# 05_LMS7002M_1_RF.net
KiCad netlist of a schematic drawn in Altium Designer
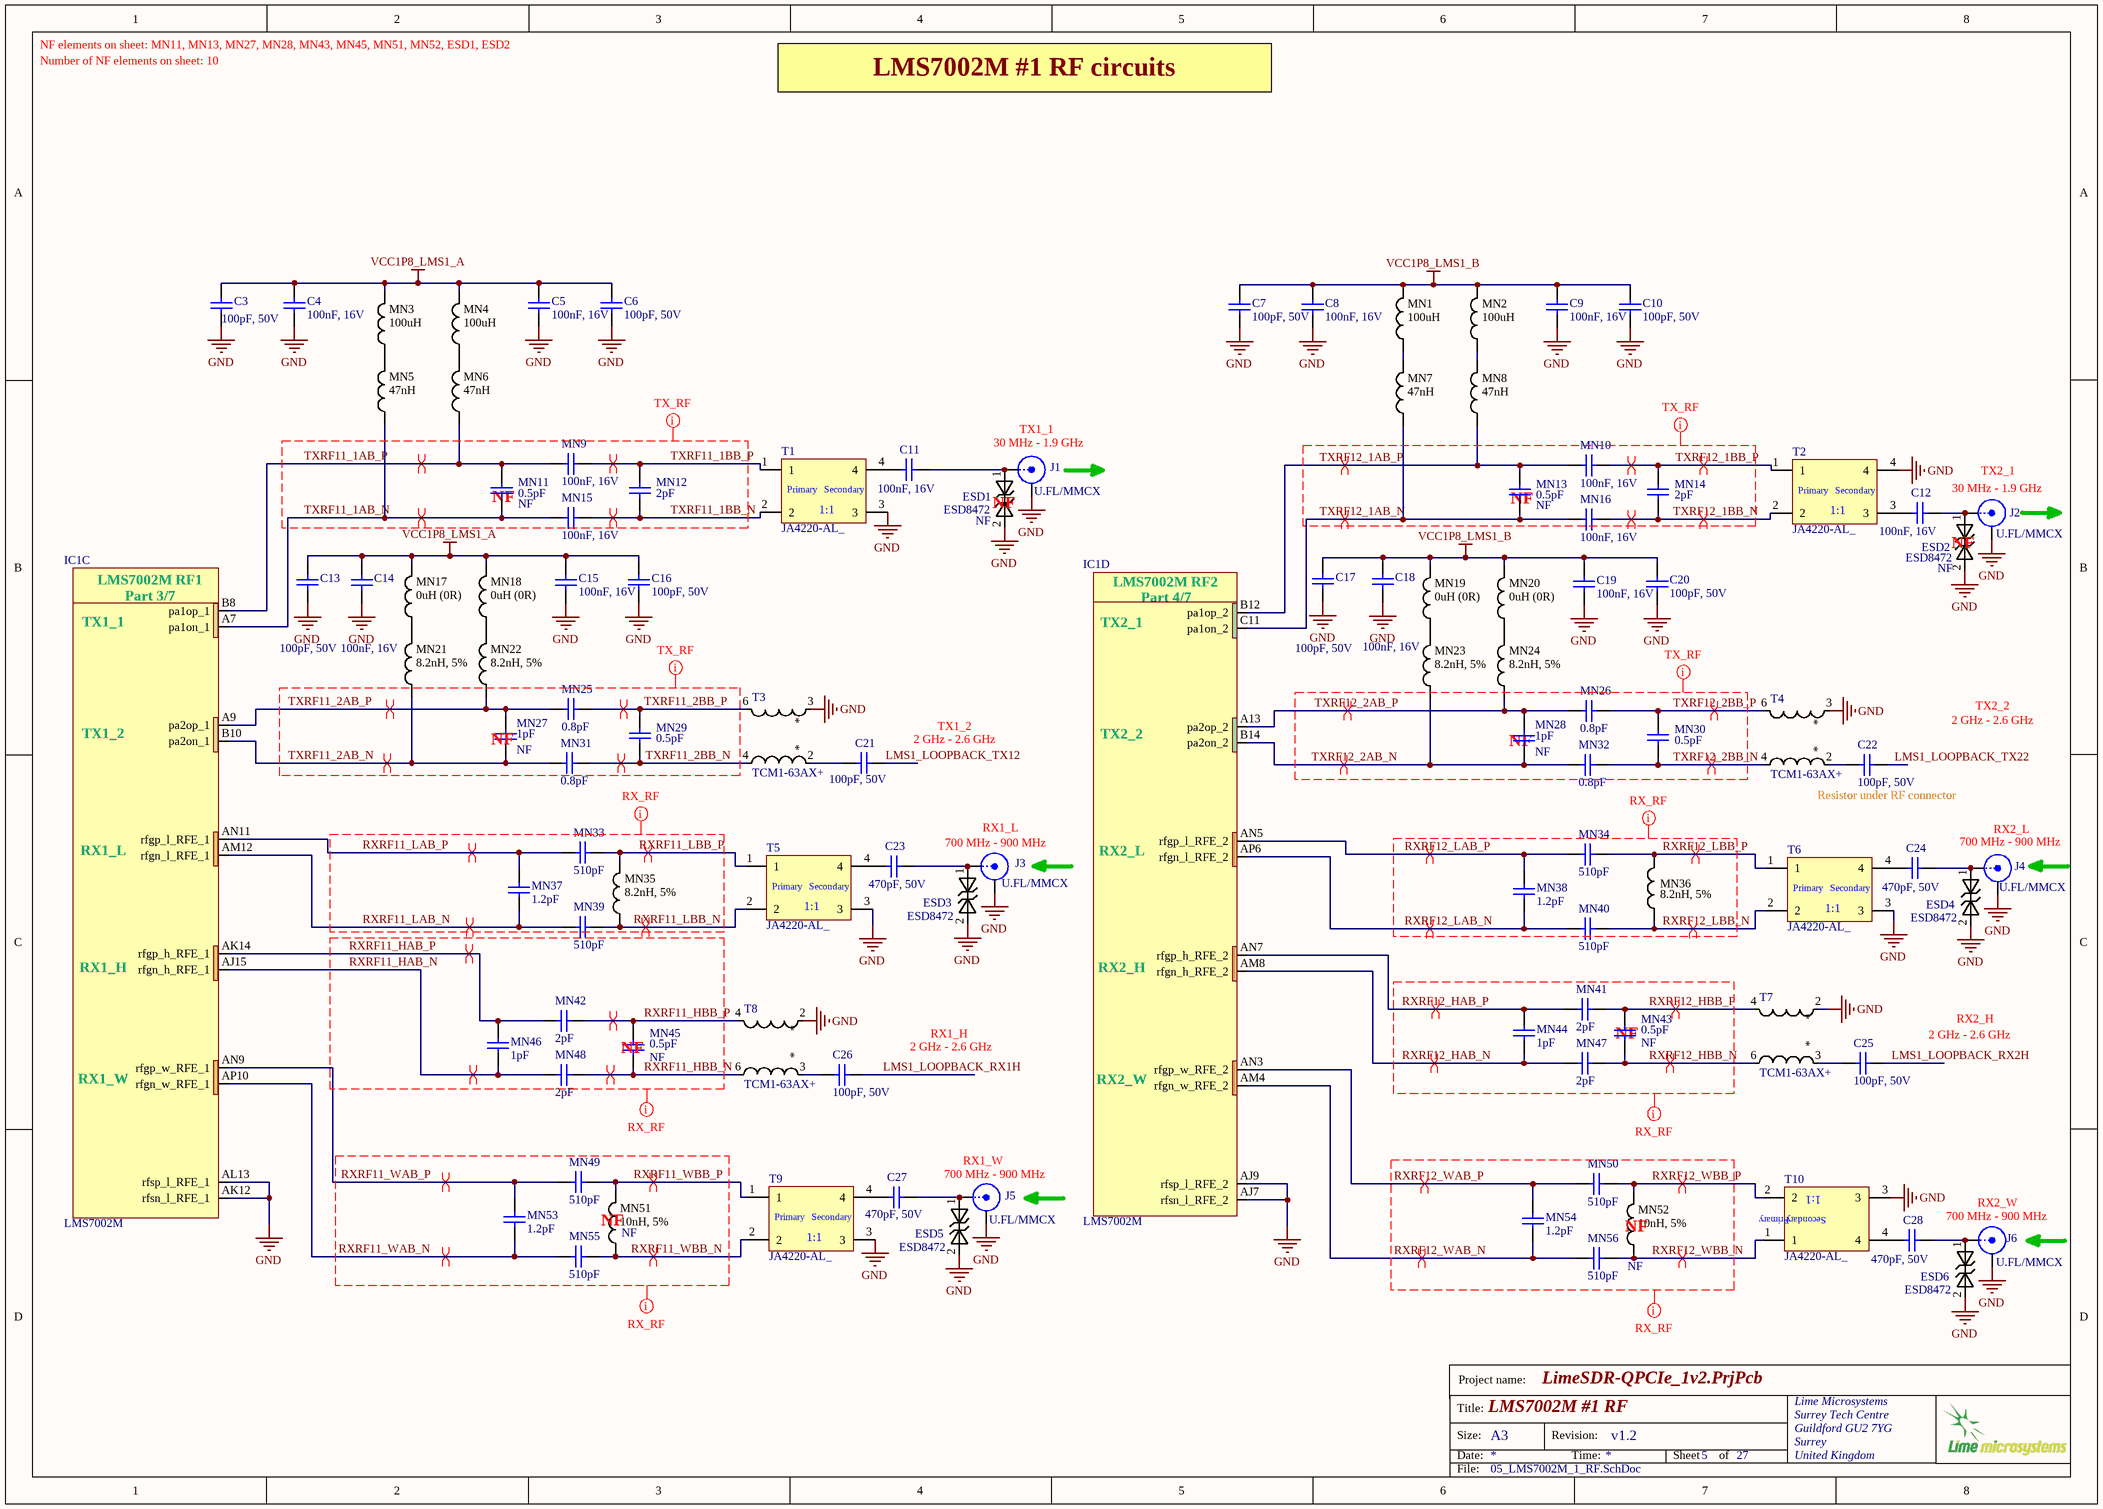
[diagram p0: 05_LMS7002M_1_RF.SchDoc]

(export (version "E")
  (design (tool "Eeschema 10.0.6"))
  (components
    (comp (ref "C3")
      (value "100pF, 50V")
      (footprint "CAP0402")
      (fields (field (name "MANUFACTURER") "Yageo") (field (name "TOLERANCE") "±5%"))
      (libsource (lib "LimeMicroAltiumLib_schLib") (part "Cap_0402"))
    )
    (comp (ref "C4")
      (value "100nF, 16V")
      (footprint "CAP0402")
      (fields
        (field (name "MANUFACTURER") "Murata Electronics")
        (field (name "TOLERANCE") "10 %")
        (field (name "MANUFACTURER PART NUMBER") "GRM155R71C104KA88D")
      )
      (libsource (lib "LimeMicroAltiumLib_schLib") (part "Cap_0402"))
    )
    (comp (ref "C5")
      (value "100nF, 16V")
      (footprint "CAP0402")
      (fields
        (field (name "MANUFACTURER") "Murata Electronics")
        (field (name "TOLERANCE") "10 %")
        (field (name "MANUFACTURER PART NUMBER") "GRM155R71C104KA88D")
      )
      (libsource (lib "LimeMicroAltiumLib_schLib") (part "Cap_0402"))
    )
    (comp (ref "C6")
      (value "100pF, 50V")
      (footprint "CAP0402")
      (fields (field (name "MANUFACTURER") "Yageo") (field (name "TOLERANCE") "±5%"))
      (libsource (lib "LimeMicroAltiumLib_schLib") (part "Cap_0402"))
    )
    (comp (ref "C7")
      (value "100pF, 50V")
      (footprint "CAP0402")
      (fields (field (name "MANUFACTURER") "Yageo") (field (name "TOLERANCE") "±5%"))
      (libsource (lib "LimeMicroAltiumLib_schLib") (part "Cap_0402"))
    )
    (comp (ref "C8")
      (value "100nF, 16V")
      (footprint "CAP0402")
      (fields
        (field (name "MANUFACTURER") "Murata Electronics")
        (field (name "TOLERANCE") "10 %")
        (field (name "MANUFACTURER PART NUMBER") "GRM155R71C104KA88D")
      )
      (libsource (lib "LimeMicroAltiumLib_schLib") (part "Cap_0402"))
    )
    (comp (ref "C9")
      (value "100nF, 16V")
      (footprint "CAP0402")
      (fields
        (field (name "MANUFACTURER") "Murata Electronics")
        (field (name "TOLERANCE") "10 %")
        (field (name "MANUFACTURER PART NUMBER") "GRM155R71C104KA88D")
      )
      (libsource (lib "LimeMicroAltiumLib_schLib") (part "Cap_0402"))
    )
    (comp (ref "C10")
      (value "100pF, 50V")
      (footprint "CAP0402")
      (fields (field (name "MANUFACTURER") "Yageo") (field (name "TOLERANCE") "±5%"))
      (libsource (lib "LimeMicroAltiumLib_schLib") (part "Cap_0402"))
    )
    (comp (ref "C11")
      (value "100nF, 16V")
      (footprint "CAP0402")
      (fields
        (field (name "MANUFACTURER") "Murata Electronics")
        (field (name "TOLERANCE") "10 %")
        (field (name "MANUFACTURER PART NUMBER") "GRM155R71C104KA88D")
      )
      (libsource (lib "LimeMicroAltiumLib_schLib") (part "Cap_0402"))
    )
    (comp (ref "C12")
      (value "100nF, 16V")
      (footprint "CAP0402")
      (fields
        (field (name "MANUFACTURER") "Murata Electronics")
        (field (name "TOLERANCE") "10 %")
        (field (name "MANUFACTURER PART NUMBER") "GRM155R71C104KA88D")
      )
      (libsource (lib "LimeMicroAltiumLib_schLib") (part "Cap_0402"))
    )
    (comp (ref "C13")
      (value "100pF, 50V")
      (footprint "CAP0402")
      (fields (field (name "MANUFACTURER") "Yageo") (field (name "TOLERANCE") "±5%"))
      (libsource (lib "LimeMicroAltiumLib_schLib") (part "Cap_0402"))
    )
    (comp (ref "C14")
      (value "100nF, 16V")
      (footprint "CAP0402")
      (fields
        (field (name "MANUFACTURER") "Murata Electronics")
        (field (name "TOLERANCE") "10 %")
        (field (name "MANUFACTURER PART NUMBER") "GRM155R71C104KA88D")
      )
      (libsource (lib "LimeMicroAltiumLib_schLib") (part "Cap_0402"))
    )
    (comp (ref "C15")
      (value "100nF, 16V")
      (footprint "CAP0402")
      (fields
        (field (name "MANUFACTURER") "Murata Electronics")
        (field (name "TOLERANCE") "10 %")
        (field (name "MANUFACTURER PART NUMBER") "GRM155R71C104KA88D")
      )
      (libsource (lib "LimeMicroAltiumLib_schLib") (part "Cap_0402"))
    )
    (comp (ref "C16")
      (value "100pF, 50V")
      (footprint "CAP0402")
      (fields (field (name "MANUFACTURER") "Yageo") (field (name "TOLERANCE") "±5%"))
      (libsource (lib "LimeMicroAltiumLib_schLib") (part "Cap_0402"))
    )
    (comp (ref "C17")
      (value "100pF, 50V")
      (footprint "CAP0402")
      (fields (field (name "MANUFACTURER") "Yageo") (field (name "TOLERANCE") "±5%"))
      (libsource (lib "LimeMicroAltiumLib_schLib") (part "Cap_0402"))
    )
    (comp (ref "C18")
      (value "100nF, 16V")
      (footprint "CAP0402")
      (fields
        (field (name "MANUFACTURER") "Murata Electronics")
        (field (name "TOLERANCE") "10 %")
        (field (name "MANUFACTURER PART NUMBER") "GRM155R71C104KA88D")
      )
      (libsource (lib "LimeMicroAltiumLib_schLib") (part "Cap_0402"))
    )
    (comp (ref "C19")
      (value "100nF, 16V")
      (footprint "CAP0402")
      (fields
        (field (name "MANUFACTURER") "Murata Electronics")
        (field (name "TOLERANCE") "10 %")
        (field (name "MANUFACTURER PART NUMBER") "GRM155R71C104KA88D")
      )
      (libsource (lib "LimeMicroAltiumLib_schLib") (part "Cap_0402"))
    )
    (comp (ref "C20")
      (value "100pF, 50V")
      (footprint "CAP0402")
      (fields (field (name "MANUFACTURER") "Yageo") (field (name "TOLERANCE") "±5%"))
      (libsource (lib "LimeMicroAltiumLib_schLib") (part "Cap_0402"))
    )
    (comp (ref "C21")
      (value "100pF, 50V")
      (footprint "CAP0402")
      (fields (field (name "TOLERANCE") "±5%") (field (name "MANUFACTURER") "Yageo"))
      (libsource (lib "LimeMicroAltiumLib_schLib") (part "Cap_0402"))
    )
    (comp (ref "C22")
      (value "100pF, 50V")
      (footprint "CAP0402")
      (fields (field (name "TOLERANCE") "±5%") (field (name "MANUFACTURER") "Yageo"))
      (libsource (lib "LimeMicroAltiumLib_schLib") (part "Cap_0402"))
    )
    (comp (ref "C23")
      (value "470pF, 50V")
      (footprint "CAP0402")
      (fields
        (field (name "MANUFACTURER PART NUMBER") "C1005C0G1H471J050BA")
        (field (name "TOLERANCE") "±5%")
        (field (name "MANUFACTURER") "TDK Corporation")
      )
      (libsource (lib "LimeMicroAltiumLib_schLib") (part "Cap_0402"))
    )
    (comp (ref "C24")
      (value "470pF, 50V")
      (footprint "CAP0402")
      (fields
        (field (name "MANUFACTURER PART NUMBER") "C1005C0G1H471J050BA")
        (field (name "TOLERANCE") "±5%")
        (field (name "MANUFACTURER") "TDK Corporation")
      )
      (libsource (lib "LimeMicroAltiumLib_schLib") (part "Cap_0402"))
    )
    (comp (ref "C25")
      (value "100pF, 50V")
      (footprint "CAP0402")
      (fields (field (name "TOLERANCE") "±5%") (field (name "MANUFACTURER") "Yageo"))
      (libsource (lib "LimeMicroAltiumLib_schLib") (part "Cap_0402"))
    )
    (comp (ref "C26")
      (value "100pF, 50V")
      (footprint "CAP0402")
      (fields (field (name "TOLERANCE") "±5%") (field (name "MANUFACTURER") "Yageo"))
      (libsource (lib "LimeMicroAltiumLib_schLib") (part "Cap_0402"))
    )
    (comp (ref "C27")
      (value "470pF, 50V")
      (footprint "CAP0402")
      (fields
        (field (name "MANUFACTURER PART NUMBER") "C1005C0G1H471J050BA")
        (field (name "TOLERANCE") "±5%")
        (field (name "MANUFACTURER") "TDK Corporation")
      )
      (libsource (lib "LimeMicroAltiumLib_schLib") (part "Cap_0402"))
    )
    (comp (ref "C28")
      (value "470pF, 50V")
      (footprint "CAP0402")
      (fields
        (field (name "MANUFACTURER PART NUMBER") "C1005C0G1H471J050BA")
        (field (name "TOLERANCE") "±5%")
        (field (name "MANUFACTURER") "TDK Corporation")
      )
      (libsource (lib "LimeMicroAltiumLib_schLib") (part "Cap_0402"))
    )
    (comp (ref "ESD1")
      (value "ESD8472")
      (footprint "ESD8472_X3DFN2")
      (fields
        (field (name "MANUFACTURER") "ON Semiconductor")
        (field (name "MANUFACTURER PART NUMBER") "ESD8472MUT5G")
        (field (name "ASSEMBLY INFO") "NF")
      )
      (libsource (lib "LimeMicroAltiumLib_schLib") (part "ESD8472"))
    )
    (comp (ref "ESD2")
      (value "ESD8472")
      (footprint "ESD8472_X3DFN2")
      (fields
        (field (name "MANUFACTURER") "ON Semiconductor")
        (field (name "MANUFACTURER PART NUMBER") "ESD8472MUT5G")
        (field (name "ASSEMBLY INFO") "NF")
      )
      (libsource (lib "LimeMicroAltiumLib_schLib") (part "ESD8472"))
    )
    (comp (ref "ESD3")
      (value "ESD8472")
      (footprint "ESD8472_X3DFN2")
      (fields
        (field (name "MANUFACTURER") "ON Semiconductor")
        (field (name "MANUFACTURER PART NUMBER") "ESD8472MUT5G")
      )
      (libsource (lib "LimeMicroAltiumLib_schLib") (part "ESD8472"))
    )
    (comp (ref "ESD4")
      (value "ESD8472")
      (footprint "ESD8472_X3DFN2")
      (fields
        (field (name "MANUFACTURER") "ON Semiconductor")
        (field (name "MANUFACTURER PART NUMBER") "ESD8472MUT5G")
      )
      (libsource (lib "LimeMicroAltiumLib_schLib") (part "ESD8472"))
    )
    (comp (ref "ESD5")
      (value "ESD8472")
      (footprint "ESD8472_X3DFN2")
      (fields
        (field (name "MANUFACTURER") "ON Semiconductor")
        (field (name "MANUFACTURER PART NUMBER") "ESD8472MUT5G")
      )
      (libsource (lib "LimeMicroAltiumLib_schLib") (part "ESD8472"))
    )
    (comp (ref "ESD6")
      (value "ESD8472")
      (footprint "ESD8472_X3DFN2")
      (fields
        (field (name "MANUFACTURER") "ON Semiconductor")
        (field (name "MANUFACTURER PART NUMBER") "ESD8472MUT5G")
      )
      (libsource (lib "LimeMicroAltiumLib_schLib") (part "ESD8472"))
    )
    (comp (ref "IC1")
      (value "LMS7002M")
      (footprint "LMS7002M_v4")
      (description "Schematic symbol revision 3. Default footprint - 0.31mm pad")
      (fields (field (name "MANUFACTURER") "Lime Microsystems"))
      (libsource (lib "LimeMicroAltiumLib_schLib") (part "LMS7002Mr3"))
    )
    (comp (ref "J1")
      (value "U.FL/MMCX")
      (footprint "MMCX_UFL_conn_u")
      (description "CONN UMC RCPT STR 50 OHM SMD")
      (fields (field (name "MANUFACTURER") "Molex, LLC"))
      (libsource (lib "LimeMicroAltiumLib_schLib") (part "RF_IF_connector"))
    )
    (comp (ref "J2")
      (value "U.FL/MMCX")
      (footprint "MMCX_UFL_conn_u")
      (description "CONN UMC RCPT STR 50 OHM SMD")
      (fields (field (name "MANUFACTURER") "Molex, LLC"))
      (libsource (lib "LimeMicroAltiumLib_schLib") (part "RF_IF_connector"))
    )
    (comp (ref "J3")
      (value "U.FL/MMCX")
      (footprint "MMCX_UFL_conn_u")
      (description "CONN UMC RCPT STR 50 OHM SMD")
      (fields (field (name "MANUFACTURER") "Molex, LLC"))
      (libsource (lib "LimeMicroAltiumLib_schLib") (part "RF_IF_connector"))
    )
    (comp (ref "J4")
      (value "U.FL/MMCX")
      (footprint "MMCX_UFL_conn_u")
      (description "CONN UMC RCPT STR 50 OHM SMD")
      (fields (field (name "MANUFACTURER") "Molex, LLC"))
      (libsource (lib "LimeMicroAltiumLib_schLib") (part "RF_IF_connector"))
    )
    (comp (ref "J5")
      (value "U.FL/MMCX")
      (footprint "MMCX_UFL_conn_u")
      (description "CONN UMC RCPT STR 50 OHM SMD")
      (fields (field (name "MANUFACTURER") "Molex, LLC"))
      (libsource (lib "LimeMicroAltiumLib_schLib") (part "RF_IF_connector"))
    )
    (comp (ref "J6")
      (value "U.FL/MMCX")
      (footprint "MMCX_UFL_conn_u")
      (description "CONN UMC RCPT STR 50 OHM SMD")
      (fields (field (name "MANUFACTURER") "Molex, LLC"))
      (libsource (lib "LimeMicroAltiumLib_schLib") (part "RF_IF_connector"))
    )
    (comp (ref "MN1")
      (value "100uH")
      (footprint "RES0805")
      (fields
        (field (name "TOLERANCE") "±10%")
        (field (name "MANUFACTURER") "TDK Corporation")
        (field (name "MANUFACTURER PART NUMBER") "MLF2012C101KT000")
      )
      (libsource (lib "LimeMicroAltiumLib_schLib") (part "Inductor_0603"))
    )
    (comp (ref "MN2")
      (value "100uH")
      (footprint "RES0805")
      (fields
        (field (name "TOLERANCE") "±10%")
        (field (name "MANUFACTURER") "TDK Corporation")
        (field (name "MANUFACTURER PART NUMBER") "MLF2012C101KT000")
      )
      (libsource (lib "LimeMicroAltiumLib_schLib") (part "Inductor_0603"))
    )
    (comp (ref "MN3")
      (value "100uH")
      (footprint "RES0805")
      (fields
        (field (name "TOLERANCE") "±10%")
        (field (name "MANUFACTURER") "TDK Corporation")
        (field (name "MANUFACTURER PART NUMBER") "MLF2012C101KT000")
      )
      (libsource (lib "LimeMicroAltiumLib_schLib") (part "Inductor_0603"))
    )
    (comp (ref "MN4")
      (value "100uH")
      (footprint "RES0805")
      (fields
        (field (name "TOLERANCE") "±10%")
        (field (name "MANUFACTURER") "TDK Corporation")
        (field (name "MANUFACTURER PART NUMBER") "MLF2012C101KT000")
      )
      (libsource (lib "LimeMicroAltiumLib_schLib") (part "Inductor_0603"))
    )
    (comp (ref "MN5")
      (value "47nH")
      (footprint "RES0402")
      (fields
        (field (name "MANUFACTURER") "COILCRAFT")
        (field (name "MANUFACTURER PART NUMBER") "0402HP-47NXJLU")
      )
      (libsource (lib "LimeMicroAltiumLib_schLib") (part "Inductor_0603"))
    )
    (comp (ref "MN6")
      (value "47nH")
      (footprint "RES0402")
      (fields
        (field (name "MANUFACTURER") "COILCRAFT")
        (field (name "MANUFACTURER PART NUMBER") "0402HP-47NXJLU")
      )
      (libsource (lib "LimeMicroAltiumLib_schLib") (part "Inductor_0603"))
    )
    (comp (ref "MN7")
      (value "47nH")
      (footprint "RES0402")
      (fields
        (field (name "MANUFACTURER") "COILCRAFT")
        (field (name "MANUFACTURER PART NUMBER") "0402HP-47NXJLU")
      )
      (libsource (lib "LimeMicroAltiumLib_schLib") (part "Inductor_0603"))
    )
    (comp (ref "MN8")
      (value "47nH")
      (footprint "RES0402")
      (fields
        (field (name "MANUFACTURER") "COILCRAFT")
        (field (name "MANUFACTURER PART NUMBER") "0402HP-47NXJLU")
      )
      (libsource (lib "LimeMicroAltiumLib_schLib") (part "Inductor_0603"))
    )
    (comp (ref "MN9")
      (value "100nF, 16V")
      (footprint "CAP0402")
      (fields
        (field (name "MANUFACTURER") "Murata Electronics")
        (field (name "TOLERANCE") "10 %")
        (field (name "MANUFACTURER PART NUMBER") "GRM155R71C104KA88D")
      )
      (libsource (lib "LimeMicroAltiumLib_schLib") (part "Cap_0402"))
    )
    (comp (ref "MN10")
      (value "100nF, 16V")
      (footprint "CAP0402")
      (fields
        (field (name "MANUFACTURER") "Murata Electronics")
        (field (name "TOLERANCE") "10 %")
        (field (name "MANUFACTURER PART NUMBER") "GRM155R71C104KA88D")
      )
      (libsource (lib "LimeMicroAltiumLib_schLib") (part "Cap_0402"))
    )
    (comp (ref "MN11")
      (value "0.5pF")
      (footprint "CAP0402")
      (fields
        (field (name "ASSEMBLY INFO") "NF")
        (field (name "TOLERANCE") "±0.25pF")
        (field (name "MANUFACTURER") "Yageo")
      )
      (libsource (lib "LimeMicroAltiumLib_schLib") (part "Cap_0402"))
    )
    (comp (ref "MN12")
      (value "2pF")
      (footprint "CAP0402")
      (fields (field (name "MANUFACTURER") "AVX"))
      (libsource (lib "LimeMicroAltiumLib_schLib") (part "Cap_0402"))
    )
    (comp (ref "MN13")
      (value "0.5pF")
      (footprint "CAP0402")
      (fields
        (field (name "ASSEMBLY INFO") "NF")
        (field (name "TOLERANCE") "±0.25pF")
        (field (name "MANUFACTURER") "Yageo")
      )
      (libsource (lib "LimeMicroAltiumLib_schLib") (part "Cap_0402"))
    )
    (comp (ref "MN14")
      (value "2pF")
      (footprint "CAP0402")
      (fields (field (name "MANUFACTURER") "AVX"))
      (libsource (lib "LimeMicroAltiumLib_schLib") (part "Cap_0402"))
    )
    (comp (ref "MN15")
      (value "100nF, 16V")
      (footprint "CAP0402")
      (fields
        (field (name "MANUFACTURER") "Murata Electronics")
        (field (name "TOLERANCE") "10 %")
        (field (name "MANUFACTURER PART NUMBER") "GRM155R71C104KA88D")
      )
      (libsource (lib "LimeMicroAltiumLib_schLib") (part "Cap_0402"))
    )
    (comp (ref "MN16")
      (value "100nF, 16V")
      (footprint "CAP0402")
      (fields
        (field (name "MANUFACTURER") "Murata Electronics")
        (field (name "TOLERANCE") "10 %")
        (field (name "MANUFACTURER PART NUMBER") "GRM155R71C104KA88D")
      )
      (libsource (lib "LimeMicroAltiumLib_schLib") (part "Cap_0402"))
    )
    (comp (ref "MN17")
      (value "0uH (0R)")
      (footprint "RES0805")
      (fields (field (name "MANUFACTURER") "BOURNS"))
      (libsource (lib "LimeMicroAltiumLib_schLib") (part "Inductor_0603"))
    )
    (comp (ref "MN18")
      (value "0uH (0R)")
      (footprint "RES0805")
      (fields (field (name "MANUFACTURER") "BOURNS"))
      (libsource (lib "LimeMicroAltiumLib_schLib") (part "Inductor_0603"))
    )
    (comp (ref "MN19")
      (value "0uH (0R)")
      (footprint "RES0805")
      (fields (field (name "MANUFACTURER") "BOURNS"))
      (libsource (lib "LimeMicroAltiumLib_schLib") (part "Inductor_0603"))
    )
    (comp (ref "MN20")
      (value "0uH (0R)")
      (footprint "RES0805")
      (fields (field (name "MANUFACTURER") "BOURNS"))
      (libsource (lib "LimeMicroAltiumLib_schLib") (part "Inductor_0603"))
    )
    (comp (ref "MN21")
      (value "8.2nH, 5%")
      (footprint "RES0402")
      (fields (field (name "MANUFACTURER") "COILCRAFT"))
      (libsource (lib "LimeMicroAltiumLib_schLib") (part "Inductor_0603"))
    )
    (comp (ref "MN22")
      (value "8.2nH, 5%")
      (footprint "RES0402")
      (fields (field (name "MANUFACTURER") "COILCRAFT"))
      (libsource (lib "LimeMicroAltiumLib_schLib") (part "Inductor_0603"))
    )
    (comp (ref "MN23")
      (value "8.2nH, 5%")
      (footprint "RES0402")
      (fields (field (name "MANUFACTURER") "COILCRAFT"))
      (libsource (lib "LimeMicroAltiumLib_schLib") (part "Inductor_0603"))
    )
    (comp (ref "MN24")
      (value "8.2nH, 5%")
      (footprint "RES0402")
      (fields (field (name "MANUFACTURER") "COILCRAFT"))
      (libsource (lib "LimeMicroAltiumLib_schLib") (part "Inductor_0603"))
    )
    (comp (ref "MN25")
      (value "0.8pF")
      (footprint "CAP0402")
      (fields
        (field (name "TOLERANCE") "±0.1pF")
        (field (name "MANUFACTURER") "Murata Electronics North America")
      )
      (libsource (lib "LimeMicroAltiumLib_schLib") (part "Cap_0402"))
    )
    (comp (ref "MN26")
      (value "0.8pF")
      (footprint "CAP0402")
      (fields
        (field (name "TOLERANCE") "±0.1pF")
        (field (name "MANUFACTURER") "Murata Electronics North America")
      )
      (libsource (lib "LimeMicroAltiumLib_schLib") (part "Cap_0402"))
    )
    (comp (ref "MN27")
      (value "1pF")
      (footprint "CAP0402")
      (fields
        (field (name "ASSEMBLY INFO") "NF")
        (field (name "MANUFACTURER") "TDK Corporation")
        (field (name "TOLERANCE") "±0.1pF")
      )
      (libsource (lib "LimeMicroAltiumLib_schLib") (part "Cap_0402"))
    )
    (comp (ref "MN28")
      (value "1pF")
      (footprint "CAP0402")
      (fields
        (field (name "ASSEMBLY INFO") "NF")
        (field (name "MANUFACTURER") "TDK Corporation")
        (field (name "TOLERANCE") "±0.1pF")
      )
      (libsource (lib "LimeMicroAltiumLib_schLib") (part "Cap_0402"))
    )
    (comp (ref "MN29")
      (value "0.5pF")
      (footprint "CAP0402")
      (fields (field (name "TOLERANCE") "±0.25pF") (field (name "MANUFACTURER") "Yageo"))
      (libsource (lib "LimeMicroAltiumLib_schLib") (part "Cap_0402"))
    )
    (comp (ref "MN30")
      (value "0.5pF")
      (footprint "CAP0402")
      (fields (field (name "TOLERANCE") "±0.25pF") (field (name "MANUFACTURER") "Yageo"))
      (libsource (lib "LimeMicroAltiumLib_schLib") (part "Cap_0402"))
    )
    (comp (ref "MN31")
      (value "0.8pF")
      (footprint "CAP0402")
      (fields
        (field (name "TOLERANCE") "±0.1pF")
        (field (name "MANUFACTURER") "Murata Electronics North America")
      )
      (libsource (lib "LimeMicroAltiumLib_schLib") (part "Cap_0402"))
    )
    (comp (ref "MN32")
      (value "0.8pF")
      (footprint "CAP0402")
      (fields
        (field (name "TOLERANCE") "±0.1pF")
        (field (name "MANUFACTURER") "Murata Electronics North America")
      )
      (libsource (lib "LimeMicroAltiumLib_schLib") (part "Cap_0402"))
    )
    (comp (ref "MN33")
      (value "510pF")
      (footprint "CAP0402")
      (fields
        (field (name "TOLERANCE") "±5%")
        (field (name "MANUFACTURER") "Murata Electronics North America")
      )
      (libsource (lib "LimeMicroAltiumLib_schLib") (part "Cap_0402"))
    )
    (comp (ref "MN34")
      (value "510pF")
      (footprint "CAP0402")
      (fields
        (field (name "TOLERANCE") "±5%")
        (field (name "MANUFACTURER") "Murata Electronics North America")
      )
      (libsource (lib "LimeMicroAltiumLib_schLib") (part "Cap_0402"))
    )
    (comp (ref "MN35")
      (value "8.2nH, 5%")
      (footprint "RES0402")
      (fields (field (name "MANUFACTURER") "COILCRAFT"))
      (libsource (lib "LimeMicroAltiumLib_schLib") (part "Inductor_0603"))
    )
    (comp (ref "MN36")
      (value "8.2nH, 5%")
      (footprint "RES0402")
      (fields (field (name "MANUFACTURER") "COILCRAFT"))
      (libsource (lib "LimeMicroAltiumLib_schLib") (part "Inductor_0603"))
    )
    (comp (ref "MN37")
      (value "1.2pF")
      (footprint "CAP0402")
      (fields
        (field (name "MANUFACTURER") "Murata Electronics North America")
        (field (name "TOLERANCE") "±0.25pF")
      )
      (libsource (lib "LimeMicroAltiumLib_schLib") (part "Cap_0402"))
    )
    (comp (ref "MN38")
      (value "1.2pF")
      (footprint "CAP0402")
      (fields
        (field (name "MANUFACTURER") "Murata Electronics North America")
        (field (name "TOLERANCE") "±0.25pF")
      )
      (libsource (lib "LimeMicroAltiumLib_schLib") (part "Cap_0402"))
    )
    (comp (ref "MN39")
      (value "510pF")
      (footprint "CAP0402")
      (fields
        (field (name "TOLERANCE") "±5%")
        (field (name "MANUFACTURER") "Murata Electronics North America")
      )
      (libsource (lib "LimeMicroAltiumLib_schLib") (part "Cap_0402"))
    )
    (comp (ref "MN40")
      (value "510pF")
      (footprint "CAP0402")
      (fields
        (field (name "TOLERANCE") "±5%")
        (field (name "MANUFACTURER") "Murata Electronics North America")
      )
      (libsource (lib "LimeMicroAltiumLib_schLib") (part "Cap_0402"))
    )
    (comp (ref "MN41")
      (value "2pF")
      (footprint "CAP0402")
      (fields (field (name "MANUFACTURER") "AVX"))
      (libsource (lib "LimeMicroAltiumLib_schLib") (part "Cap_0402"))
    )
    (comp (ref "MN42")
      (value "2pF")
      (footprint "CAP0402")
      (fields (field (name "MANUFACTURER") "AVX"))
      (libsource (lib "LimeMicroAltiumLib_schLib") (part "Cap_0402"))
    )
    (comp (ref "MN43")
      (value "0.5pF")
      (footprint "CAP0402")
      (fields
        (field (name "ASSEMBLY INFO") "NF")
        (field (name "TOLERANCE") "±0.25pF")
        (field (name "MANUFACTURER") "Yageo")
      )
      (libsource (lib "LimeMicroAltiumLib_schLib") (part "Cap_0402"))
    )
    (comp (ref "MN44")
      (value "1pF")
      (footprint "CAP0402")
      (fields (field (name "MANUFACTURER") "TDK Corporation") (field (name "TOLERANCE") "±0.1pF"))
      (libsource (lib "LimeMicroAltiumLib_schLib") (part "Cap_0402"))
    )
    (comp (ref "MN45")
      (value "0.5pF")
      (footprint "CAP0402")
      (fields
        (field (name "ASSEMBLY INFO") "NF")
        (field (name "TOLERANCE") "±0.25pF")
        (field (name "MANUFACTURER") "Yageo")
      )
      (libsource (lib "LimeMicroAltiumLib_schLib") (part "Cap_0402"))
    )
    (comp (ref "MN46")
      (value "1pF")
      (footprint "CAP0402")
      (fields (field (name "MANUFACTURER") "TDK Corporation") (field (name "TOLERANCE") "±0.1pF"))
      (libsource (lib "LimeMicroAltiumLib_schLib") (part "Cap_0402"))
    )
    (comp (ref "MN47")
      (value "2pF")
      (footprint "CAP0402")
      (fields (field (name "MANUFACTURER") "AVX"))
      (libsource (lib "LimeMicroAltiumLib_schLib") (part "Cap_0402"))
    )
    (comp (ref "MN48")
      (value "2pF")
      (footprint "CAP0402")
      (fields (field (name "MANUFACTURER") "AVX"))
      (libsource (lib "LimeMicroAltiumLib_schLib") (part "Cap_0402"))
    )
    (comp (ref "MN49")
      (value "510pF")
      (footprint "CAP0402")
      (fields
        (field (name "TOLERANCE") "±5%")
        (field (name "MANUFACTURER") "Murata Electronics North America")
      )
      (libsource (lib "LimeMicroAltiumLib_schLib") (part "Cap_0402"))
    )
    (comp (ref "MN50")
      (value "510pF")
      (footprint "CAP0402")
      (fields
        (field (name "TOLERANCE") "±5%")
        (field (name "MANUFACTURER") "Murata Electronics North America")
      )
      (libsource (lib "LimeMicroAltiumLib_schLib") (part "Cap_0402"))
    )
    (comp (ref "MN51")
      (value "10nH, 5%")
      (footprint "RES0402")
      (fields (field (name "MANUFACTURER") "COILCRAFT") (field (name "ASSEMBLY INFO") "NF"))
      (libsource (lib "LimeMicroAltiumLib_schLib") (part "Inductor_0603"))
    )
    (comp (ref "MN52")
      (value "10nH, 5%")
      (footprint "RES0402")
      (fields (field (name "MANUFACTURER") "COILCRAFT") (field (name "ASSEMBLY INFO") "NF"))
      (libsource (lib "LimeMicroAltiumLib_schLib") (part "Inductor_0603"))
    )
    (comp (ref "MN53")
      (value "1.2pF")
      (footprint "CAP0402")
      (fields
        (field (name "MANUFACTURER") "Murata Electronics North America")
        (field (name "TOLERANCE") "±0.25pF")
      )
      (libsource (lib "LimeMicroAltiumLib_schLib") (part "Cap_0402"))
    )
    (comp (ref "MN54")
      (value "1.2pF")
      (footprint "CAP0402")
      (fields
        (field (name "MANUFACTURER") "Murata Electronics North America")
        (field (name "TOLERANCE") "±0.25pF")
      )
      (libsource (lib "LimeMicroAltiumLib_schLib") (part "Cap_0402"))
    )
    (comp (ref "MN55")
      (value "510pF")
      (footprint "CAP0402")
      (fields
        (field (name "TOLERANCE") "±5%")
        (field (name "MANUFACTURER") "Murata Electronics North America")
      )
      (libsource (lib "LimeMicroAltiumLib_schLib") (part "Cap_0402"))
    )
    (comp (ref "MN56")
      (value "510pF")
      (footprint "CAP0402")
      (fields
        (field (name "TOLERANCE") "±5%")
        (field (name "MANUFACTURER") "Murata Electronics North America")
      )
      (libsource (lib "LimeMicroAltiumLib_schLib") (part "Cap_0402"))
    )
    (comp (ref "T1")
      (value "JA4220-AL_")
      (footprint "JA4220-AL_")
      (fields (field (name "MANUFACTURER") "Coilcraft"))
      (libsource (lib "") (part "JA4220-AL__1"))
    )
    (comp (ref "T2")
      (value "JA4220-AL_")
      (footprint "JA4220-AL_")
      (fields (field (name "MANUFACTURER") "Coilcraft"))
      (libsource (lib "") (part "JA4220-AL__1"))
    )
    (comp (ref "T3")
      (value "TCM1-63AX+")
      (footprint "TCM1-63AX+_v2")
      (fields (field (name "MANUFACTURER") "Mini-circuits"))
      (libsource (lib "LimeMicroAltiumLib_schLib") (part "Balun_v2"))
    )
    (comp (ref "T4")
      (value "TCM1-63AX+")
      (footprint "TCM1-63AX+_v2")
      (fields (field (name "MANUFACTURER") "Mini-circuits"))
      (libsource (lib "LimeMicroAltiumLib_schLib") (part "Balun_v2"))
    )
    (comp (ref "T5")
      (value "JA4220-AL_")
      (footprint "JA4220-AL_")
      (fields (field (name "MANUFACTURER") "Coilcraft"))
      (libsource (lib "") (part "JA4220-AL__1"))
    )
    (comp (ref "T6")
      (value "JA4220-AL_")
      (footprint "JA4220-AL_")
      (fields (field (name "MANUFACTURER") "Coilcraft"))
      (libsource (lib "") (part "JA4220-AL__1"))
    )
    (comp (ref "T7")
      (value "TCM1-63AX+")
      (footprint "TCM1-63AX+_v2")
      (fields (field (name "MANUFACTURER") "Mini-circuits"))
      (libsource (lib "") (part "Balun_v2_1"))
    )
    (comp (ref "T8")
      (value "TCM1-63AX+")
      (footprint "TCM1-63AX+_v2")
      (fields (field (name "MANUFACTURER") "Mini-circuits"))
      (libsource (lib "") (part "Balun_v2_1"))
    )
    (comp (ref "T9")
      (value "JA4220-AL_")
      (footprint "JA4220-AL_")
      (fields (field (name "MANUFACTURER") "Coilcraft"))
      (libsource (lib "") (part "JA4220-AL__1"))
    )
    (comp (ref "T10")
      (value "JA4220-AL_")
      (footprint "JA4220-AL_")
      (fields (field (name "MANUFACTURER") "Coilcraft"))
      (libsource (lib "LimeMicroAltiumLib_schLib") (part "JA4220-AL_"))
    )
  )
  (nets
    (net (code "1") (name "/LMS1_LOOPBACK_RX1H") (class "Default")
      (node (ref "C26") (pin "1") (pinfunction "1_1") (pintype "passive"))
    )
    (net (code "2") (name "/LMS1_LOOPBACK_RX2H") (class "Default")
      (node (ref "C25") (pin "1") (pinfunction "1_1") (pintype "passive"))
    )
    (net (code "3") (name "/LMS1_LOOPBACK_TX12") (class "Default")
      (node (ref "C21") (pin "1") (pinfunction "1_1") (pintype "passive"))
    )
    (net (code "4") (name "/LMS1_LOOPBACK_TX22") (class "Default")
      (node (ref "C22") (pin "1") (pinfunction "1_1") (pintype "passive"))
    )
    (net (code "5") (name "/RXRF11_HAB_N") (class "Default")
      (node (ref "IC1") (pin "AJ15") (pinfunction "rfgn_h_RFE_1_AJ15") (pintype "passive"))
      (node (ref "MN46") (pin "1") (pinfunction "1_1") (pintype "passive"))
      (node (ref "MN48") (pin "2") (pinfunction "2_2") (pintype "passive"))
    )
    (net (code "6") (name "/RXRF11_HAB_P") (class "Default")
      (node (ref "IC1") (pin "AK14") (pinfunction "rfgp_h_RFE_1_AK14") (pintype "passive"))
      (node (ref "MN42") (pin "2") (pinfunction "2_2") (pintype "passive"))
      (node (ref "MN46") (pin "2") (pinfunction "2_2") (pintype "passive"))
    )
    (net (code "7") (name "/RXRF11_HBB_N") (class "Default")
      (node (ref "MN45") (pin "1") (pinfunction "1_1") (pintype "passive"))
      (node (ref "MN48") (pin "1") (pinfunction "1_1") (pintype "passive"))
      (node (ref "T8") (pin "6") (pinfunction "6_6") (pintype "passive"))
    )
    (net (code "8") (name "/RXRF11_HBB_P") (class "Default")
      (node (ref "MN42") (pin "1") (pinfunction "1_1") (pintype "passive"))
      (node (ref "MN45") (pin "2") (pinfunction "2_2") (pintype "passive"))
      (node (ref "T8") (pin "4") (pinfunction "4_4") (pintype "passive"))
    )
    (net (code "9") (name "/RXRF11_LAB_N") (class "Default")
      (node (ref "IC1") (pin "AM12") (pinfunction "rfgn_l_RFE_1_AM12") (pintype "passive"))
      (node (ref "MN37") (pin "1") (pinfunction "1_1") (pintype "passive"))
      (node (ref "MN39") (pin "2") (pinfunction "2_2") (pintype "passive"))
    )
    (net (code "10") (name "/RXRF11_LAB_P") (class "Default")
      (node (ref "IC1") (pin "AN11") (pinfunction "rfgp_l_RFE_1_AN11") (pintype "passive"))
      (node (ref "MN33") (pin "2") (pinfunction "2_2") (pintype "passive"))
      (node (ref "MN37") (pin "2") (pinfunction "2_2") (pintype "passive"))
    )
    (net (code "11") (name "/RXRF11_LBB_N") (class "Default")
      (node (ref "MN35") (pin "1") (pinfunction "1_1") (pintype "passive"))
      (node (ref "MN39") (pin "1") (pinfunction "1_1") (pintype "passive"))
      (node (ref "T5") (pin "2") (pinfunction "2_2") (pintype "passive"))
    )
    (net (code "12") (name "/RXRF11_LBB_P") (class "Default")
      (node (ref "MN33") (pin "1") (pinfunction "1_1") (pintype "passive"))
      (node (ref "MN35") (pin "2") (pinfunction "2_2") (pintype "passive"))
      (node (ref "T5") (pin "1") (pinfunction "1_1") (pintype "passive"))
    )
    (net (code "13") (name "/RXRF11_WAB_N") (class "Default")
      (node (ref "IC1") (pin "AP10") (pinfunction "rfgn_w_RFE_1_AP10") (pintype "passive"))
      (node (ref "MN53") (pin "2") (pinfunction "2_2") (pintype "passive"))
      (node (ref "MN55") (pin "2") (pinfunction "2_2") (pintype "passive"))
    )
    (net (code "14") (name "/RXRF11_WAB_P") (class "Default")
      (node (ref "IC1") (pin "AN9") (pinfunction "rfgp_w_RFE_1_AN9") (pintype "passive"))
      (node (ref "MN49") (pin "2") (pinfunction "2_2") (pintype "passive"))
      (node (ref "MN53") (pin "1") (pinfunction "1_1") (pintype "passive"))
    )
    (net (code "15") (name "/RXRF11_WBB_N") (class "Default")
      (node (ref "MN51") (pin "1") (pinfunction "1_1") (pintype "passive"))
      (node (ref "MN55") (pin "1") (pinfunction "1_1") (pintype "passive"))
      (node (ref "T9") (pin "2") (pinfunction "2_2") (pintype "passive"))
    )
    (net (code "16") (name "/RXRF11_WBB_P") (class "Default")
      (node (ref "MN49") (pin "1") (pinfunction "1_1") (pintype "passive"))
      (node (ref "MN51") (pin "2") (pinfunction "2_2") (pintype "passive"))
      (node (ref "T9") (pin "1") (pinfunction "1_1") (pintype "passive"))
    )
    (net (code "17") (name "/RXRF12_HAB_N") (class "Default")
      (node (ref "IC1") (pin "AM8") (pinfunction "rfgn_h_RFE_2_AM8") (pintype "passive"))
      (node (ref "MN44") (pin "1") (pinfunction "1_1") (pintype "passive"))
      (node (ref "MN47") (pin "2") (pinfunction "2_2") (pintype "passive"))
    )
    (net (code "18") (name "/RXRF12_HAB_P") (class "Default")
      (node (ref "IC1") (pin "AN7") (pinfunction "rfgp_h_RFE_2_AN7") (pintype "passive"))
      (node (ref "MN41") (pin "2") (pinfunction "2_2") (pintype "passive"))
      (node (ref "MN44") (pin "2") (pinfunction "2_2") (pintype "passive"))
    )
    (net (code "19") (name "/RXRF12_HBB_N") (class "Default")
      (node (ref "MN43") (pin "1") (pinfunction "1_1") (pintype "passive"))
      (node (ref "MN47") (pin "1") (pinfunction "1_1") (pintype "passive"))
      (node (ref "T7") (pin "6") (pinfunction "6_6") (pintype "passive"))
    )
    (net (code "20") (name "/RXRF12_HBB_P") (class "Default")
      (node (ref "MN41") (pin "1") (pinfunction "1_1") (pintype "passive"))
      (node (ref "MN43") (pin "2") (pinfunction "2_2") (pintype "passive"))
      (node (ref "T7") (pin "4") (pinfunction "4_4") (pintype "passive"))
    )
    (net (code "21") (name "/RXRF12_LAB_N") (class "Default")
      (node (ref "IC1") (pin "AP6") (pinfunction "rfgn_l_RFE_2_AP6") (pintype "passive"))
      (node (ref "MN38") (pin "1") (pinfunction "1_1") (pintype "passive"))
      (node (ref "MN40") (pin "2") (pinfunction "2_2") (pintype "passive"))
    )
    (net (code "22") (name "/RXRF12_LAB_P") (class "Default")
      (node (ref "IC1") (pin "AN5") (pinfunction "rfgp_l_RFE_2_AN5") (pintype "passive"))
      (node (ref "MN34") (pin "2") (pinfunction "2_2") (pintype "passive"))
      (node (ref "MN38") (pin "2") (pinfunction "2_2") (pintype "passive"))
    )
    (net (code "23") (name "/RXRF12_LBB_N") (class "Default")
      (node (ref "MN36") (pin "1") (pinfunction "1_1") (pintype "passive"))
      (node (ref "MN40") (pin "1") (pinfunction "1_1") (pintype "passive"))
      (node (ref "T6") (pin "2") (pinfunction "2_2") (pintype "passive"))
    )
    (net (code "24") (name "/RXRF12_LBB_P") (class "Default")
      (node (ref "MN34") (pin "1") (pinfunction "1_1") (pintype "passive"))
      (node (ref "MN36") (pin "2") (pinfunction "2_2") (pintype "passive"))
      (node (ref "T6") (pin "1") (pinfunction "1_1") (pintype "passive"))
    )
    (net (code "25") (name "/RXRF12_WAB_N") (class "Default")
      (node (ref "IC1") (pin "AM4") (pinfunction "rfgn_w_RFE_2_AM4") (pintype "passive"))
      (node (ref "MN54") (pin "2") (pinfunction "2_2") (pintype "passive"))
      (node (ref "MN56") (pin "2") (pinfunction "2_2") (pintype "passive"))
    )
    (net (code "26") (name "/RXRF12_WAB_P") (class "Default")
      (node (ref "IC1") (pin "AN3") (pinfunction "rfgp_w_RFE_2_AN3") (pintype "passive"))
      (node (ref "MN50") (pin "2") (pinfunction "2_2") (pintype "passive"))
      (node (ref "MN54") (pin "1") (pinfunction "1_1") (pintype "passive"))
    )
    (net (code "27") (name "/RXRF12_WBB_N") (class "Default")
      (node (ref "MN52") (pin "1") (pinfunction "1_1") (pintype "passive"))
      (node (ref "MN56") (pin "1") (pinfunction "1_1") (pintype "passive"))
      (node (ref "T10") (pin "1") (pinfunction "1_1") (pintype "passive"))
    )
    (net (code "28") (name "/RXRF12_WBB_P") (class "Default")
      (node (ref "MN50") (pin "1") (pinfunction "1_1") (pintype "passive"))
      (node (ref "MN52") (pin "2") (pinfunction "2_2") (pintype "passive"))
      (node (ref "T10") (pin "2") (pinfunction "2_2") (pintype "passive"))
    )
    (net (code "29") (name "/TXRF11_1AB_N") (class "Default")
      (node (ref "IC1") (pin "A7") (pinfunction "pa1on_1_A7") (pintype "passive"))
      (node (ref "MN11") (pin "1") (pinfunction "1_1") (pintype "passive"))
      (node (ref "MN15") (pin "1") (pinfunction "1_1") (pintype "passive"))
      (node (ref "MN5") (pin "1") (pinfunction "1_1") (pintype "passive"))
    )
    (net (code "30") (name "/TXRF11_1AB_P") (class "Default")
      (node (ref "IC1") (pin "B8") (pinfunction "pa1op_1_B8") (pintype "passive"))
      (node (ref "MN11") (pin "2") (pinfunction "2_2") (pintype "passive"))
      (node (ref "MN6") (pin "1") (pinfunction "1_1") (pintype "passive"))
      (node (ref "MN9") (pin "2") (pinfunction "2_2") (pintype "passive"))
    )
    (net (code "31") (name "/TXRF11_1BB_N") (class "Default")
      (node (ref "MN12") (pin "1") (pinfunction "1_1") (pintype "passive"))
      (node (ref "MN15") (pin "2") (pinfunction "2_2") (pintype "passive"))
      (node (ref "T1") (pin "2") (pinfunction "2_2") (pintype "passive"))
    )
    (net (code "32") (name "/TXRF11_1BB_P") (class "Default")
      (node (ref "MN12") (pin "2") (pinfunction "2_2") (pintype "passive"))
      (node (ref "MN9") (pin "1") (pinfunction "1_1") (pintype "passive"))
      (node (ref "T1") (pin "1") (pinfunction "1_1") (pintype "passive"))
    )
    (net (code "33") (name "/TXRF11_2AB_N") (class "Default")
      (node (ref "IC1") (pin "B10") (pinfunction "pa2on_1_B10") (pintype "passive"))
      (node (ref "MN21") (pin "1") (pinfunction "1_1") (pintype "passive"))
      (node (ref "MN27") (pin "2") (pinfunction "2_2") (pintype "passive"))
      (node (ref "MN31") (pin "2") (pinfunction "2_2") (pintype "passive"))
    )
    (net (code "34") (name "/TXRF11_2AB_P") (class "Default")
      (node (ref "IC1") (pin "A9") (pinfunction "pa2op_1_A9") (pintype "passive"))
      (node (ref "MN22") (pin "1") (pinfunction "1_1") (pintype "passive"))
      (node (ref "MN25") (pin "2") (pinfunction "2_2") (pintype "passive"))
      (node (ref "MN27") (pin "1") (pinfunction "1_1") (pintype "passive"))
    )
    (net (code "35") (name "/TXRF11_2BB_N") (class "Default")
      (node (ref "MN29") (pin "1") (pinfunction "1_1") (pintype "passive"))
      (node (ref "MN31") (pin "1") (pinfunction "1_1") (pintype "passive"))
      (node (ref "T3") (pin "4") (pinfunction "4_4") (pintype "passive"))
    )
    (net (code "36") (name "/TXRF11_2BB_P") (class "Default")
      (node (ref "MN25") (pin "1") (pinfunction "1_1") (pintype "passive"))
      (node (ref "MN29") (pin "2") (pinfunction "2_2") (pintype "passive"))
      (node (ref "T3") (pin "6") (pinfunction "6_6") (pintype "passive"))
    )
    (net (code "37") (name "/TXRF12_1AB_N") (class "Default")
      (node (ref "IC1") (pin "C11") (pinfunction "pa1on_2_C11") (pintype "passive"))
      (node (ref "MN13") (pin "1") (pinfunction "1_1") (pintype "passive"))
      (node (ref "MN16") (pin "1") (pinfunction "1_1") (pintype "passive"))
      (node (ref "MN7") (pin "1") (pinfunction "1_1") (pintype "passive"))
    )
    (net (code "38") (name "/TXRF12_1AB_P") (class "Default")
      (node (ref "IC1") (pin "B12") (pinfunction "pa1op_2_B12") (pintype "passive"))
      (node (ref "MN10") (pin "2") (pinfunction "2_2") (pintype "passive"))
      (node (ref "MN13") (pin "2") (pinfunction "2_2") (pintype "passive"))
      (node (ref "MN8") (pin "1") (pinfunction "1_1") (pintype "passive"))
    )
    (net (code "39") (name "/TXRF12_1BB_N") (class "Default")
      (node (ref "MN14") (pin "1") (pinfunction "1_1") (pintype "passive"))
      (node (ref "MN16") (pin "2") (pinfunction "2_2") (pintype "passive"))
      (node (ref "T2") (pin "2") (pinfunction "2_2") (pintype "passive"))
    )
    (net (code "40") (name "/TXRF12_1BB_P") (class "Default")
      (node (ref "MN10") (pin "1") (pinfunction "1_1") (pintype "passive"))
      (node (ref "MN14") (pin "2") (pinfunction "2_2") (pintype "passive"))
      (node (ref "T2") (pin "1") (pinfunction "1_1") (pintype "passive"))
    )
    (net (code "41") (name "/TXRF12_2AB_N") (class "Default")
      (node (ref "IC1") (pin "B14") (pinfunction "pa2on_2_B14") (pintype "passive"))
      (node (ref "MN23") (pin "1") (pinfunction "1_1") (pintype "passive"))
      (node (ref "MN28") (pin "2") (pinfunction "2_2") (pintype "passive"))
      (node (ref "MN32") (pin "2") (pinfunction "2_2") (pintype "passive"))
    )
    (net (code "42") (name "/TXRF12_2AB_P") (class "Default")
      (node (ref "IC1") (pin "A13") (pinfunction "pa2op_2_A13") (pintype "passive"))
      (node (ref "MN24") (pin "1") (pinfunction "1_1") (pintype "passive"))
      (node (ref "MN26") (pin "2") (pinfunction "2_2") (pintype "passive"))
      (node (ref "MN28") (pin "1") (pinfunction "1_1") (pintype "passive"))
    )
    (net (code "43") (name "/TXRF12_2BB_N") (class "Default")
      (node (ref "MN30") (pin "1") (pinfunction "1_1") (pintype "passive"))
      (node (ref "MN32") (pin "1") (pinfunction "1_1") (pintype "passive"))
      (node (ref "T4") (pin "4") (pinfunction "4_4") (pintype "passive"))
    )
    (net (code "44") (name "/TXRF12_2BB_P") (class "Default")
      (node (ref "MN26") (pin "1") (pinfunction "1_1") (pintype "passive"))
      (node (ref "MN30") (pin "2") (pinfunction "2_2") (pintype "passive"))
      (node (ref "T4") (pin "6") (pinfunction "6_6") (pintype "passive"))
    )
    (net (code "45") (name "GND") (class "Default")
      (node (ref "C10") (pin "2") (pinfunction "2_2") (pintype "passive"))
      (node (ref "C13") (pin "2") (pinfunction "2_2") (pintype "passive"))
      (node (ref "C14") (pin "1") (pinfunction "1_1") (pintype "passive"))
      (node (ref "C15") (pin "1") (pinfunction "1_1") (pintype "passive"))
      (node (ref "C16") (pin "2") (pinfunction "2_2") (pintype "passive"))
      (node (ref "C17") (pin "2") (pinfunction "2_2") (pintype "passive"))
      (node (ref "C18") (pin "1") (pinfunction "1_1") (pintype "passive"))
      (node (ref "C19") (pin "1") (pinfunction "1_1") (pintype "passive"))
      (node (ref "C20") (pin "2") (pinfunction "2_2") (pintype "passive"))
      (node (ref "C3") (pin "2") (pinfunction "2_2") (pintype "passive"))
      (node (ref "C4") (pin "1") (pinfunction "1_1") (pintype "passive"))
      (node (ref "C5") (pin "1") (pinfunction "1_1") (pintype "passive"))
      (node (ref "C6") (pin "2") (pinfunction "2_2") (pintype "passive"))
      (node (ref "C7") (pin "2") (pinfunction "2_2") (pintype "passive"))
      (node (ref "C8") (pin "1") (pinfunction "1_1") (pintype "passive"))
      (node (ref "C9") (pin "1") (pinfunction "1_1") (pintype "passive"))
      (node (ref "ESD1") (pin "2") (pinfunction "2_2") (pintype "passive"))
      (node (ref "ESD2") (pin "2") (pinfunction "2_2") (pintype "passive"))
      (node (ref "ESD3") (pin "2") (pinfunction "2_2") (pintype "passive"))
      (node (ref "ESD4") (pin "2") (pinfunction "2_2") (pintype "passive"))
      (node (ref "ESD5") (pin "2") (pinfunction "2_2") (pintype "passive"))
      (node (ref "ESD6") (pin "2") (pinfunction "2_2") (pintype "passive"))
      (node (ref "IC1") (pin "AJ7") (pinfunction "rfsn_l_RFE_2_AJ7") (pintype "passive"))
      (node (ref "IC1") (pin "AJ9") (pinfunction "rfsp_l_RFE_2_AJ9") (pintype "passive"))
      (node (ref "IC1") (pin "AK12") (pinfunction "rfsn_l_RFE_1_AK12") (pintype "passive"))
      (node (ref "IC1") (pin "AL13") (pinfunction "rfsp_l_RFE_1_AL13") (pintype "passive"))
      (node (ref "J1") (pin "2") (pinfunction "Y_2") (pintype "passive"))
      (node (ref "J2") (pin "2") (pinfunction "Y_2") (pintype "passive"))
      (node (ref "J3") (pin "2") (pinfunction "Y_2") (pintype "passive"))
      (node (ref "J4") (pin "2") (pinfunction "Y_2") (pintype "passive"))
      (node (ref "J5") (pin "2") (pinfunction "Y_2") (pintype "passive"))
      (node (ref "J6") (pin "2") (pinfunction "Y_2") (pintype "passive"))
      (node (ref "T1") (pin "3") (pinfunction "3_3") (pintype "passive"))
      (node (ref "T10") (pin "3") (pinfunction "3_3") (pintype "passive"))
      (node (ref "T2") (pin "4") (pinfunction "4_4") (pintype "passive"))
      (node (ref "T3") (pin "3") (pinfunction "3_3") (pintype "passive"))
      (node (ref "T4") (pin "3") (pinfunction "3_3") (pintype "passive"))
      (node (ref "T5") (pin "3") (pinfunction "3_3") (pintype "passive"))
      (node (ref "T6") (pin "3") (pinfunction "3_3") (pintype "passive"))
      (node (ref "T7") (pin "2") (pinfunction "2_2") (pintype "passive"))
      (node (ref "T8") (pin "2") (pinfunction "2_2") (pintype "passive"))
      (node (ref "T9") (pin "3") (pinfunction "3_3") (pintype "passive"))
    )
    (net (code "46") (name "Net-(C11-Pad2)") (class "Default")
      (node (ref "C11") (pin "2") (pinfunction "2_2") (pintype "passive"))
      (node (ref "T1") (pin "4") (pinfunction "4_4") (pintype "passive"))
    )
    (net (code "47") (name "Net-(C12-Pad2)") (class "Default")
      (node (ref "C12") (pin "2") (pinfunction "2_2") (pintype "passive"))
      (node (ref "T2") (pin "3") (pinfunction "3_3") (pintype "passive"))
    )
    (net (code "48") (name "Net-(C21-Pad2)") (class "Default")
      (node (ref "C21") (pin "2") (pinfunction "2_2") (pintype "passive"))
      (node (ref "T3") (pin "2") (pinfunction "2_2") (pintype "passive"))
    )
    (net (code "49") (name "Net-(C22-Pad2)") (class "Default")
      (node (ref "C22") (pin "2") (pinfunction "2_2") (pintype "passive"))
      (node (ref "T4") (pin "2") (pinfunction "2_2") (pintype "passive"))
    )
    (net (code "50") (name "Net-(C23-Pad2)") (class "Default")
      (node (ref "C23") (pin "2") (pinfunction "2_2") (pintype "passive"))
      (node (ref "T5") (pin "4") (pinfunction "4_4") (pintype "passive"))
    )
    (net (code "51") (name "Net-(C24-Pad2)") (class "Default")
      (node (ref "C24") (pin "2") (pinfunction "2_2") (pintype "passive"))
      (node (ref "T6") (pin "4") (pinfunction "4_4") (pintype "passive"))
    )
    (net (code "52") (name "Net-(C25-Pad2)") (class "Default")
      (node (ref "C25") (pin "2") (pinfunction "2_2") (pintype "passive"))
      (node (ref "T7") (pin "3") (pinfunction "3_3") (pintype "passive"))
    )
    (net (code "53") (name "Net-(C26-Pad2)") (class "Default")
      (node (ref "C26") (pin "2") (pinfunction "2_2") (pintype "passive"))
      (node (ref "T8") (pin "3") (pinfunction "3_3") (pintype "passive"))
    )
    (net (code "54") (name "Net-(C27-Pad2)") (class "Default")
      (node (ref "C27") (pin "2") (pinfunction "2_2") (pintype "passive"))
      (node (ref "T9") (pin "4") (pinfunction "4_4") (pintype "passive"))
    )
    (net (code "55") (name "Net-(C28-Pad2)") (class "Default")
      (node (ref "C28") (pin "2") (pinfunction "2_2") (pintype "passive"))
      (node (ref "T10") (pin "4") (pinfunction "4_4") (pintype "passive"))
    )
    (net (code "56") (name "Net-(J1-X)") (class "Default")
      (node (ref "C11") (pin "1") (pinfunction "1_1") (pintype "passive"))
      (node (ref "ESD1") (pin "1") (pinfunction "1_1") (pintype "passive"))
      (node (ref "J1") (pin "1") (pinfunction "X_1") (pintype "passive"))
    )
    (net (code "57") (name "Net-(J2-X)") (class "Default")
      (node (ref "C12") (pin "1") (pinfunction "1_1") (pintype "passive"))
      (node (ref "ESD2") (pin "1") (pinfunction "1_1") (pintype "passive"))
      (node (ref "J2") (pin "1") (pinfunction "X_1") (pintype "passive"))
    )
    (net (code "58") (name "Net-(J3-X)") (class "Default")
      (node (ref "C23") (pin "1") (pinfunction "1_1") (pintype "passive"))
      (node (ref "ESD3") (pin "1") (pinfunction "1_1") (pintype "passive"))
      (node (ref "J3") (pin "1") (pinfunction "X_1") (pintype "passive"))
    )
    (net (code "59") (name "Net-(J4-X)") (class "Default")
      (node (ref "C24") (pin "1") (pinfunction "1_1") (pintype "passive"))
      (node (ref "ESD4") (pin "1") (pinfunction "1_1") (pintype "passive"))
      (node (ref "J4") (pin "1") (pinfunction "X_1") (pintype "passive"))
    )
    (net (code "60") (name "Net-(J5-X)") (class "Default")
      (node (ref "C27") (pin "1") (pinfunction "1_1") (pintype "passive"))
      (node (ref "ESD5") (pin "1") (pinfunction "1_1") (pintype "passive"))
      (node (ref "J5") (pin "1") (pinfunction "X_1") (pintype "passive"))
    )
    (net (code "61") (name "Net-(J6-X)") (class "Default")
      (node (ref "C28") (pin "1") (pinfunction "1_1") (pintype "passive"))
      (node (ref "ESD6") (pin "1") (pinfunction "1_1") (pintype "passive"))
      (node (ref "J6") (pin "1") (pinfunction "X_1") (pintype "passive"))
    )
    (net (code "62") (name "Net-(MN1-Pad1)") (class "Default")
      (node (ref "MN1") (pin "1") (pinfunction "1_1") (pintype "passive"))
      (node (ref "MN7") (pin "2") (pinfunction "2_2") (pintype "passive"))
    )
    (net (code "63") (name "Net-(MN2-Pad1)") (class "Default")
      (node (ref "MN2") (pin "1") (pinfunction "1_1") (pintype "passive"))
      (node (ref "MN8") (pin "2") (pinfunction "2_2") (pintype "passive"))
    )
    (net (code "64") (name "Net-(MN3-Pad1)") (class "Default")
      (node (ref "MN3") (pin "1") (pinfunction "1_1") (pintype "passive"))
      (node (ref "MN5") (pin "2") (pinfunction "2_2") (pintype "passive"))
    )
    (net (code "65") (name "Net-(MN4-Pad1)") (class "Default")
      (node (ref "MN4") (pin "1") (pinfunction "1_1") (pintype "passive"))
      (node (ref "MN6") (pin "2") (pinfunction "2_2") (pintype "passive"))
    )
    (net (code "66") (name "Net-(MN17-Pad1)") (class "Default")
      (node (ref "MN17") (pin "1") (pinfunction "1_1") (pintype "passive"))
      (node (ref "MN21") (pin "2") (pinfunction "2_2") (pintype "passive"))
    )
    (net (code "67") (name "Net-(MN18-Pad1)") (class "Default")
      (node (ref "MN18") (pin "1") (pinfunction "1_1") (pintype "passive"))
      (node (ref "MN22") (pin "2") (pinfunction "2_2") (pintype "passive"))
    )
    (net (code "68") (name "Net-(MN19-Pad1)") (class "Default")
      (node (ref "MN19") (pin "1") (pinfunction "1_1") (pintype "passive"))
      (node (ref "MN23") (pin "2") (pinfunction "2_2") (pintype "passive"))
    )
    (net (code "69") (name "Net-(MN20-Pad1)") (class "Default")
      (node (ref "MN20") (pin "1") (pinfunction "1_1") (pintype "passive"))
      (node (ref "MN24") (pin "2") (pinfunction "2_2") (pintype "passive"))
    )
    (net (code "70") (name "VCC1P8_LMS1_A") (class "Default")
      (node (ref "C13") (pin "1") (pinfunction "1_1") (pintype "passive"))
      (node (ref "C14") (pin "2") (pinfunction "2_2") (pintype "passive"))
      (node (ref "C15") (pin "2") (pinfunction "2_2") (pintype "passive"))
      (node (ref "C16") (pin "1") (pinfunction "1_1") (pintype "passive"))
      (node (ref "C3") (pin "1") (pinfunction "1_1") (pintype "passive"))
      (node (ref "C4") (pin "2") (pinfunction "2_2") (pintype "passive"))
      (node (ref "C5") (pin "2") (pinfunction "2_2") (pintype "passive"))
      (node (ref "C6") (pin "1") (pinfunction "1_1") (pintype "passive"))
      (node (ref "MN17") (pin "2") (pinfunction "2_2") (pintype "passive"))
      (node (ref "MN18") (pin "2") (pinfunction "2_2") (pintype "passive"))
      (node (ref "MN3") (pin "2") (pinfunction "2_2") (pintype "passive"))
      (node (ref "MN4") (pin "2") (pinfunction "2_2") (pintype "passive"))
    )
    (net (code "71") (name "VCC1P8_LMS1_B") (class "Default")
      (node (ref "C10") (pin "1") (pinfunction "1_1") (pintype "passive"))
      (node (ref "C17") (pin "1") (pinfunction "1_1") (pintype "passive"))
      (node (ref "C18") (pin "2") (pinfunction "2_2") (pintype "passive"))
      (node (ref "C19") (pin "2") (pinfunction "2_2") (pintype "passive"))
      (node (ref "C20") (pin "1") (pinfunction "1_1") (pintype "passive"))
      (node (ref "C7") (pin "1") (pinfunction "1_1") (pintype "passive"))
      (node (ref "C8") (pin "2") (pinfunction "2_2") (pintype "passive"))
      (node (ref "C9") (pin "2") (pinfunction "2_2") (pintype "passive"))
      (node (ref "MN1") (pin "2") (pinfunction "2_2") (pintype "passive"))
      (node (ref "MN19") (pin "2") (pinfunction "2_2") (pintype "passive"))
      (node (ref "MN2") (pin "2") (pinfunction "2_2") (pintype "passive"))
      (node (ref "MN20") (pin "2") (pinfunction "2_2") (pintype "passive"))
    )
  )
)
